# MCT-1601-ss.net
KiCad netlist of a schematic drawn in EAGLE
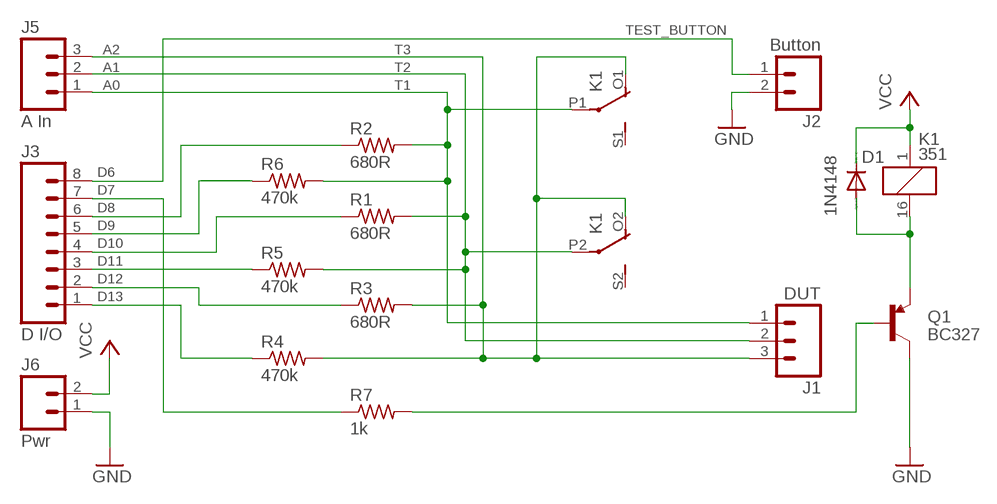
[diagram p0: schematic, sheet 1]

(export (version "E")
  (design (tool "Eeschema 10.0.6"))
  (components
    (comp (ref "D1")
      (value "1N4148")
      (footprint "eagle-import:D-2.5")
      (libsource (lib "eagle-import") (part "DIODE-D-2.5"))
    )
    (comp (ref "J1")
      (value "DUT")
      (footprint "eagle-import:1X03")
      (libsource (lib "eagle-import") (part "M03PTH"))
    )
    (comp (ref "J2")
      (value "Button")
      (footprint "eagle-import:1X02")
      (libsource (lib "eagle-import") (part "M02PTH"))
    )
    (comp (ref "J3")
      (value "D I/O")
      (footprint "eagle-import:1X08_ROUND")
      (libsource (lib "eagle-import") (part "M08"))
    )
    (comp (ref "J5")
      (value "A In")
      (footprint "eagle-import:1X03")
      (libsource (lib "eagle-import") (part "M03PTH"))
    )
    (comp (ref "J6")
      (value "Pwr")
      (footprint "eagle-import:1X02")
      (libsource (lib "eagle-import") (part "M02PTH"))
    )
    (comp (ref "K1")
      (value "351")
      (footprint "eagle-import:351")
      (libsource (lib "eagle-import") (part "351"))
    )
    (comp (ref "Q1")
      (value "BC327")
      (footprint "eagle-import:TO-92")
      (libsource (lib "eagle-import") (part "SS-PNP-BC327"))
    )
    (comp (ref "R1")
      (value "680R")
      (footprint "eagle-import:0204_5")
      (libsource (lib "eagle-import") (part "R-US_0204/5"))
    )
    (comp (ref "R2")
      (value "680R")
      (footprint "eagle-import:0204_5")
      (libsource (lib "eagle-import") (part "R-US_0204/5"))
    )
    (comp (ref "R3")
      (value "680R")
      (footprint "eagle-import:0204_5")
      (libsource (lib "eagle-import") (part "R-US_0204/5"))
    )
    (comp (ref "R4")
      (value "470k")
      (footprint "eagle-import:0204_5")
      (libsource (lib "eagle-import") (part "R-US_0204/5"))
    )
    (comp (ref "R5")
      (value "470k")
      (footprint "eagle-import:0204_5")
      (libsource (lib "eagle-import") (part "R-US_0204/5"))
    )
    (comp (ref "R6")
      (value "470k")
      (footprint "eagle-import:0204_5")
      (libsource (lib "eagle-import") (part "R-US_0204/5"))
    )
    (comp (ref "R7")
      (value "1k")
      (footprint "eagle-import:0204_5")
      (libsource (lib "eagle-import") (part "R-US_0204/5"))
    )
  )
  (nets
    (net (code "1") (name "/D7") (class "Default")
      (node (ref "J3") (pin "7") (pinfunction "7_7") (pintype "passive"))
      (node (ref "R7") (pin "1") (pinfunction "1_1") (pintype "passive"))
    )
    (net (code "2") (name "/D8") (class "Default")
      (node (ref "J3") (pin "6") (pinfunction "6_6") (pintype "passive"))
      (node (ref "R2") (pin "1") (pinfunction "1_1") (pintype "passive"))
    )
    (net (code "3") (name "/D9") (class "Default")
      (node (ref "J3") (pin "5") (pinfunction "5_5") (pintype "passive"))
      (node (ref "R6") (pin "1") (pinfunction "1_1") (pintype "passive"))
    )
    (net (code "4") (name "/D10") (class "Default")
      (node (ref "J3") (pin "4") (pinfunction "4_4") (pintype "passive"))
      (node (ref "R1") (pin "1") (pinfunction "1_1") (pintype "passive"))
    )
    (net (code "5") (name "/D11") (class "Default")
      (node (ref "J3") (pin "3") (pinfunction "3_3") (pintype "passive"))
      (node (ref "R5") (pin "1") (pinfunction "1_1") (pintype "passive"))
    )
    (net (code "6") (name "/D12") (class "Default")
      (node (ref "J3") (pin "2") (pinfunction "2_2") (pintype "passive"))
      (node (ref "R3") (pin "1") (pinfunction "1_1") (pintype "passive"))
    )
    (net (code "7") (name "/D13") (class "Default")
      (node (ref "J3") (pin "1") (pinfunction "1_1") (pintype "passive"))
      (node (ref "R4") (pin "1") (pinfunction "1_1") (pintype "passive"))
    )
    (net (code "8") (name "/T1") (class "Default")
      (node (ref "J1") (pin "1") (pinfunction "1_1") (pintype "passive"))
      (node (ref "J5") (pin "1") (pinfunction "1_1") (pintype "passive"))
      (node (ref "K1") (pin "P1") (pinfunction "P_P1") (pintype "passive"))
      (node (ref "R2") (pin "2") (pinfunction "2_2") (pintype "passive"))
      (node (ref "R6") (pin "2") (pinfunction "2_2") (pintype "passive"))
    )
    (net (code "9") (name "/T2") (class "Default")
      (node (ref "J1") (pin "2") (pinfunction "2_2") (pintype "passive"))
      (node (ref "J5") (pin "2") (pinfunction "2_2") (pintype "passive"))
      (node (ref "K1") (pin "P2") (pinfunction "P_P2") (pintype "passive"))
      (node (ref "R1") (pin "2") (pinfunction "2_2") (pintype "passive"))
      (node (ref "R5") (pin "2") (pinfunction "2_2") (pintype "passive"))
    )
    (net (code "10") (name "/T3") (class "Default")
      (node (ref "J1") (pin "3") (pinfunction "3_3") (pintype "passive"))
      (node (ref "J5") (pin "3") (pinfunction "3_3") (pintype "passive"))
      (node (ref "K1") (pin "O1") (pinfunction "O_O1") (pintype "passive"))
      (node (ref "K1") (pin "O2") (pinfunction "O_O2") (pintype "passive"))
      (node (ref "R3") (pin "2") (pinfunction "2_2") (pintype "passive"))
      (node (ref "R4") (pin "2") (pinfunction "2_2") (pintype "passive"))
    )
    (net (code "11") (name "/TEST_BUTTON") (class "Default")
      (node (ref "J2") (pin "1") (pinfunction "1_1") (pintype "passive"))
      (node (ref "J3") (pin "8") (pinfunction "8_8") (pintype "passive"))
    )
    (net (code "12") (name "GND") (class "Default")
      (node (ref "J2") (pin "2") (pinfunction "2_2") (pintype "passive"))
      (node (ref "J6") (pin "1") (pinfunction "1_1") (pintype "passive"))
      (node (ref "Q1") (pin "3") (pinfunction "C_3") (pintype "passive"))
    )
    (net (code "13") (name "Net-(K1A-2)") (class "Default")
      (node (ref "D1") (pin "A") (pinfunction "A_A") (pintype "passive"))
      (node (ref "K1") (pin "16") (pinfunction "2_16") (pintype "passive"))
      (node (ref "Q1") (pin "1") (pinfunction "E_1") (pintype "passive"))
    )
    (net (code "14") (name "Net-(Q1-B)") (class "Default")
      (node (ref "Q1") (pin "2") (pinfunction "B_2") (pintype "passive"))
      (node (ref "R7") (pin "2") (pinfunction "2_2") (pintype "passive"))
    )
    (net (code "15") (name "VCC") (class "Default")
      (node (ref "D1") (pin "C") (pinfunction "C_C") (pintype "passive"))
      (node (ref "J6") (pin "2") (pinfunction "2_2") (pintype "passive"))
      (node (ref "K1") (pin "1") (pinfunction "1_1") (pintype "passive"))
    )
    (net (code "16") (name "unconnected-(K1B-S-PadS1)") (class "Default")
      (node (ref "K1") (pin "S1") (pinfunction "S_S1") (pintype "passive"))
    )
    (net (code "17") (name "unconnected-(K1C-S-PadS2)") (class "Default")
      (node (ref "K1") (pin "S2") (pinfunction "S_S2") (pintype "passive"))
    )
  )
)
